# Filter.net
KiCad netlist of a schematic drawn in Altium Designer
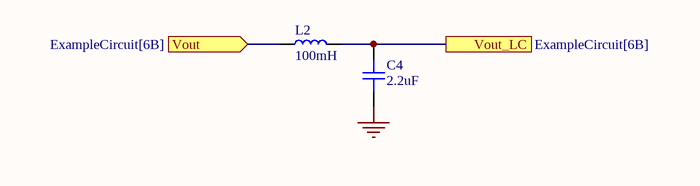
[diagram p0: Filter.SchDoc]

(export (version "E")
  (design (tool "Eeschema 10.0.6"))
  (components
    (comp (ref "C4")
      (value "2.2uF")
      (footprint "CAP_0603")
      (description "Capacitor SMD 0603")
      (libsource (lib "PhilsLabLib.") (part "CAP_0603"))
    )
    (comp (ref "L2")
      (value "100mH")
      (footprint "IND_0603")
      (description "Inductor SMD 0603")
      (libsource (lib "PhilsLabLib.") (part "IND_0603"))
    )
  )
  (nets
    (net (code "1") (name "/Vout") (class "Default")
      (node (ref "L2") (pin "1") (pinfunction "1_1") (pintype "passive"))
    )
    (net (code "2") (name "/Vout_LC") (class "Default")
      (node (ref "C4") (pin "1") (pinfunction "1_1") (pintype "passive"))
      (node (ref "L2") (pin "2") (pinfunction "2_2") (pintype "passive"))
    )
    (net (code "3") (name "GND") (class "Default")
      (node (ref "C4") (pin "2") (pinfunction "2_2") (pintype "passive"))
    )
  )
)
